# radios.net
KiCad netlist of a schematic drawn in Altium Designer
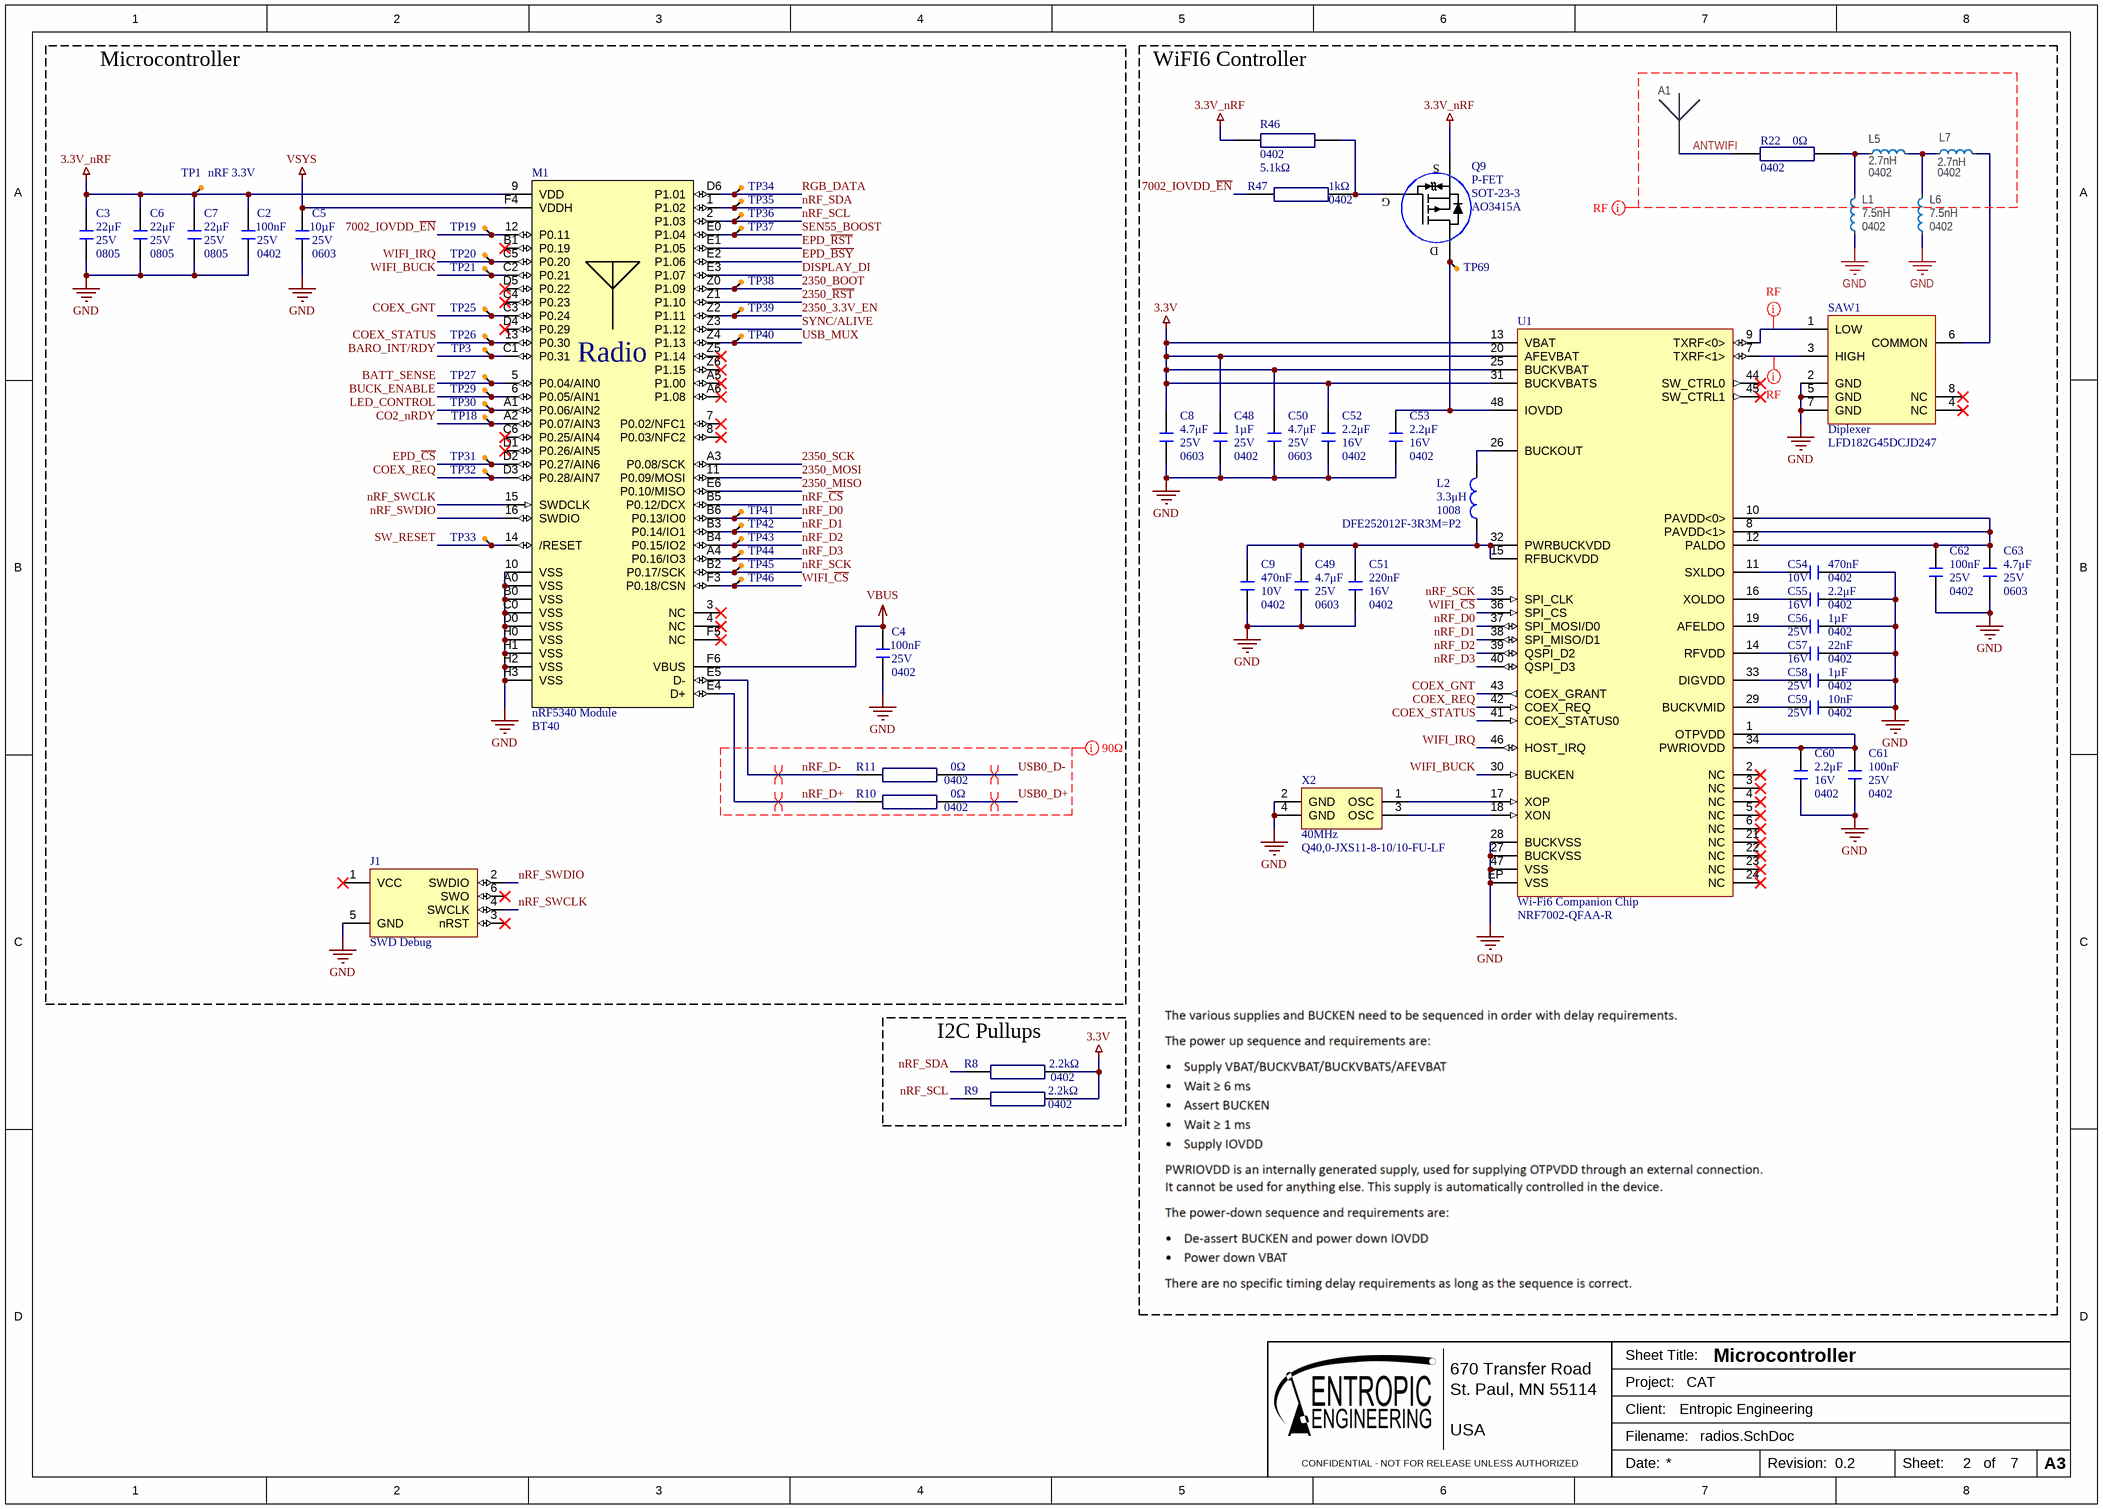
[diagram p0: radios.SchDoc]

(export (version "E")
  (design (tool "Eeschema 10.0.6"))
  (components
    (comp (ref "A1")
      (value "~")
      (footprint "NN03-320")
      (description "Dual-Band GNSS and Wi-Fi/BluetoothAntenna")
      (fields
        (field (name "PART NUMBER") "NN03-320")
        (field (name "MANUFACTURER") "Ignion")
        (field (name "AUTHOR") "rubr")
      )
      (libsource (lib "cat") (part "Antenna_NN03-320"))
    )
    (comp (ref "C2")
      (value "GRM155R71E104KE14D")
      (footprint "0402_capacitor")
      (description "100 nF, 25 V, X7R, 0402 Chip capacitor")
      (fields
        (field (name "MANUFACTURER") "Murata")
        (field (name "TOLERANCE") "10%")
        (field (name "VOLTAGE RATING") "25V")
        (field (name "CASE CODE (IMPERIAL)") "0402")
        (field (name "CAPACITANCE") "100nF")
      )
      (libsource (lib "cat") (part "GRM155R71E104KE14D"))
    )
    (comp (ref "C3")
      (value "22μF")
      (footprint "0805_capacitor")
      (description "22 μF, 25 V, X5R, 0805 Chip capacitor")
      (fields
        (field (name "MANUFACTURER") "Murata")
        (field (name "MANUFACTURER PART NUMBER") "GRT21BR61E226ME13L")
        (field (name "RATED DC VOLTAGE (URDC)") "25V")
        (field (name "CASE/PACKAGE") "0805")
      )
      (libsource (lib "cat") (part "GRT21BR61E226ME13L"))
    )
    (comp (ref "C4")
      (value "GRM155R71E104KE14D")
      (footprint "0402_capacitor")
      (description "100 nF, 25 V, X7R, 0402 Chip capacitor")
      (fields
        (field (name "MANUFACTURER") "Murata")
        (field (name "TOLERANCE") "10%")
        (field (name "VOLTAGE RATING") "25V")
        (field (name "CASE CODE (IMPERIAL)") "0402")
        (field (name "CAPACITANCE") "100nF")
      )
      (libsource (lib "cat") (part "GRM155R71E104KE14D"))
    )
    (comp (ref "C5")
      (value "10µF")
      (footprint "0603_capacitor")
      (description "10 µF, 25 V, X5R, 0603 Chip capacitor")
      (fields
        (field (name "MANUFACTURER") "Samsung")
        (field (name "TOLERANCE") "20%")
        (field (name "VOLTAGE RATING") "25V")
        (field (name "CASE CODE (IMPERIAL)") "0603")
      )
      (libsource (lib "cat") (part "CL10A106MA8NRNC"))
    )
    (comp (ref "C6")
      (value "22μF")
      (footprint "0805_capacitor")
      (description "22 μF, 25 V, X5R, 0805 Chip capacitor")
      (fields
        (field (name "MANUFACTURER") "Murata")
        (field (name "MANUFACTURER PART NUMBER") "GRT21BR61E226ME13L")
        (field (name "RATED DC VOLTAGE (URDC)") "25V")
        (field (name "CASE/PACKAGE") "0805")
      )
      (libsource (lib "cat") (part "GRT21BR61E226ME13L"))
    )
    (comp (ref "C7")
      (value "22μF")
      (footprint "0805_capacitor")
      (description "22 μF, 25 V, X5R, 0805 Chip capacitor")
      (fields
        (field (name "MANUFACTURER") "Murata")
        (field (name "MANUFACTURER PART NUMBER") "GRT21BR61E226ME13L")
        (field (name "RATED DC VOLTAGE (URDC)") "25V")
        (field (name "CASE/PACKAGE") "0805")
      )
      (libsource (lib "cat") (part "GRT21BR61E226ME13L"))
    )
    (comp (ref "C8")
      (value "4.7μF")
      (footprint "0603_capacitor")
      (description "4.7 μF, 25 V, X7R, 0603 Chip capacitor")
      (fields
        (field (name "MANUFACTURER") "TDK")
        (field (name "MANUFACTURER PART NUMBER") "C1608X5R1E475K080AC")
        (field (name "VOLTAGE RATING") "25V")
        (field (name "CASE/PACKAGE") "0603")
      )
      (libsource (lib "cat") (part "C1608X5R1E475K080AC"))
    )
    (comp (ref "C9")
      (value "CL05Y474KP5VPJC")
      (footprint "0402_capacitor")
      (description "470 nF, 10 V, X7S, 0402 Chip capacitor")
      (fields
        (field (name "MANUFACTURER") "Samsung")
        (field (name "CAPACITANCE") "470nF")
        (field (name "VOLTAGE RATING") "10V")
        (field (name "CASE/PACKAGE") "0402")
      )
      (libsource (lib "cat") (part "CL05Y474KP5VPJC"))
    )
    (comp (ref "C48")
      (value "GRM155R61E105KA12D")
      (footprint "0402_capacitor")
      (description "1 µF, 25 V, X5R, 0402 Chip capacitor")
      (fields
        (field (name "MANUFACTURER") "Murata")
        (field (name "HOUSE_PART_NUMBER") "C-1uF-0402-002")
        (field (name "SIZE CODE") "0402")
        (field (name "CAPACITANCE") "1µF")
        (field (name "VOLTAGE") "25V")
      )
      (libsource (lib "cat") (part "GRM155R61E105KA12D"))
    )
    (comp (ref "C49")
      (value "4.7μF")
      (footprint "0603_capacitor")
      (description "4.7 μF, 25 V, X7R, 0603 Chip capacitor")
      (fields
        (field (name "MANUFACTURER") "TDK")
        (field (name "MANUFACTURER PART NUMBER") "C1608X5R1E475K080AC")
        (field (name "VOLTAGE RATING") "25V")
        (field (name "CASE/PACKAGE") "0603")
      )
      (libsource (lib "cat") (part "C1608X5R1E475K080AC"))
    )
    (comp (ref "C50")
      (value "4.7μF")
      (footprint "0603_capacitor")
      (description "4.7 μF, 25 V, X7R, 0603 Chip capacitor")
      (fields
        (field (name "MANUFACTURER") "TDK")
        (field (name "MANUFACTURER PART NUMBER") "C1608X5R1E475K080AC")
        (field (name "VOLTAGE RATING") "25V")
        (field (name "CASE/PACKAGE") "0603")
      )
      (libsource (lib "cat") (part "C1608X5R1E475K080AC"))
    )
    (comp (ref "C51")
      (value "220nF")
      (footprint "0402_capacitor")
      (description "220 nF, 16 V, X7R, 0402 Chip capacitor")
      (fields
        (field (name "MANUFACTURER") "Murata")
        (field (name "MANUFACTURER PART NUMBER") "GCM155R71C224KE02D")
        (field (name "VOLTAGE RATING") "16V")
        (field (name "CASE/PACKAGE") "0402")
      )
      (libsource (lib "cat") (part "GCM155R71C224KE02D"))
    )
    (comp (ref "C52")
      (value "2.2μF")
      (footprint "0402_capacitor")
      (description "2.2 µF, 16 V, X7T, 0402 Chip capacitor")
      (fields
        (field (name "MANUFACTURER") "Murata")
        (field (name "MANUFACTURER PART NUMBER") "GRM155D71C225ME11D")
        (field (name "VOLTAGE RATING") "16V")
        (field (name "CASE/PACKAGE") "0402")
      )
      (libsource (lib "cat") (part "GRM155D71C225ME11D"))
    )
    (comp (ref "C53")
      (value "2.2μF")
      (footprint "0402_capacitor")
      (description "2.2 µF, 16 V, X7T, 0402 Chip capacitor")
      (fields
        (field (name "MANUFACTURER") "Murata")
        (field (name "MANUFACTURER PART NUMBER") "GRM155D71C225ME11D")
        (field (name "VOLTAGE RATING") "16V")
        (field (name "CASE/PACKAGE") "0402")
      )
      (libsource (lib "cat") (part "GRM155D71C225ME11D"))
    )
    (comp (ref "C54")
      (value "CL05Y474KP5VPJC")
      (footprint "0402_capacitor")
      (description "470 nF, 10 V, X7S, 0402 Chip capacitor")
      (fields
        (field (name "MANUFACTURER") "Samsung")
        (field (name "CAPACITANCE") "470nF")
        (field (name "VOLTAGE RATING") "10V")
        (field (name "CASE/PACKAGE") "0402")
      )
      (libsource (lib "cat") (part "CL05Y474KP5VPJC"))
    )
    (comp (ref "C55")
      (value "2.2μF")
      (footprint "0402_capacitor")
      (description "2.2 µF, 16 V, X7T, 0402 Chip capacitor")
      (fields
        (field (name "MANUFACTURER") "Murata")
        (field (name "MANUFACTURER PART NUMBER") "GRM155D71C225ME11D")
        (field (name "VOLTAGE RATING") "16V")
        (field (name "CASE/PACKAGE") "0402")
      )
      (libsource (lib "cat") (part "GRM155D71C225ME11D"))
    )
    (comp (ref "C56")
      (value "GRM155R61E105KA12D")
      (footprint "0402_capacitor")
      (description "1 µF, 25 V, X5R, 0402 Chip capacitor")
      (fields
        (field (name "MANUFACTURER") "Murata")
        (field (name "HOUSE_PART_NUMBER") "C-1uF-0402-002")
        (field (name "SIZE CODE") "0402")
        (field (name "CAPACITANCE") "1µF")
        (field (name "VOLTAGE") "25V")
      )
      (libsource (lib "cat") (part "GRM155R61E105KA12D"))
    )
    (comp (ref "C57")
      (value "22nF")
      (footprint "0402_capacitor")
      (description "22 nF, 16 V, X7R, 0402 Chip capacitor")
      (fields
        (field (name "MANUFACTURER") "KEMET")
        (field (name "MANUFACTURER PART NUMBER") "C0402C223K4RECAUTO")
        (field (name "VOLTAGE RATING") "16V")
        (field (name "CASE/PACKAGE") "0402")
      )
      (libsource (lib "cat") (part "C0402C223K4RECAUTO"))
    )
    (comp (ref "C58")
      (value "GRM155R61E105KA12D")
      (footprint "0402_capacitor")
      (description "1 µF, 25 V, X5R, 0402 Chip capacitor")
      (fields
        (field (name "MANUFACTURER") "Murata")
        (field (name "HOUSE_PART_NUMBER") "C-1uF-0402-002")
        (field (name "SIZE CODE") "0402")
        (field (name "CAPACITANCE") "1µF")
        (field (name "VOLTAGE") "25V")
      )
      (libsource (lib "cat") (part "GRM155R61E105KA12D"))
    )
    (comp (ref "C59")
      (value "CL05B103KA5NNNC")
      (footprint "0402_capacitor")
      (description "10 nF, 25 V, X7R, 0402 Chip capacitor")
      (fields
        (field (name "MANUFACTURER") "Samsung")
        (field (name "TOLERANCE") "10%")
        (field (name "CAPACITANCE") "10nF")
        (field (name "VOLTAGE RATING") "25V")
        (field (name "CASE CODE (IMPERIAL)") "0402")
      )
      (libsource (lib "cat") (part "CL05B103KA5NNNC"))
    )
    (comp (ref "C60")
      (value "2.2μF")
      (footprint "0402_capacitor")
      (description "2.2 µF, 16 V, X7T, 0402 Chip capacitor")
      (fields
        (field (name "MANUFACTURER") "Murata")
        (field (name "MANUFACTURER PART NUMBER") "GRM155D71C225ME11D")
        (field (name "VOLTAGE RATING") "16V")
        (field (name "CASE/PACKAGE") "0402")
      )
      (libsource (lib "cat") (part "GRM155D71C225ME11D"))
    )
    (comp (ref "C61")
      (value "GRM155R71E104KE14D")
      (footprint "0402_capacitor")
      (description "100 nF, 25 V, X7R, 0402 Chip capacitor")
      (fields
        (field (name "MANUFACTURER") "Murata")
        (field (name "TOLERANCE") "10%")
        (field (name "CASE CODE (IMPERIAL)") "0402")
        (field (name "VOLTAGE") "25V")
        (field (name "CAPACITANCE") "100nF")
      )
      (libsource (lib "cat") (part "GRM155R71E104KE14D"))
    )
    (comp (ref "C62")
      (value "GRM155R71E104KE14D")
      (footprint "0402_capacitor")
      (description "100 nF, 25 V, X7R, 0402 Chip capacitor")
      (fields
        (field (name "MANUFACTURER") "Murata")
        (field (name "TOLERANCE") "10%")
        (field (name "CASE CODE (IMPERIAL)") "0402")
        (field (name "VOLTAGE") "25V")
        (field (name "CAPACITANCE") "100nF")
      )
      (libsource (lib "cat") (part "GRM155R71E104KE14D"))
    )
    (comp (ref "C63")
      (value "4.7μF")
      (footprint "0603_capacitor")
      (description "4.7 μF, 25 V, X7R, 0603 Chip capacitor")
      (fields
        (field (name "MANUFACTURER") "TDK")
        (field (name "MANUFACTURER PART NUMBER") "C1608X5R1E475K080AC")
        (field (name "VOLTAGE RATING") "25V")
        (field (name "CASE/PACKAGE") "0603")
      )
      (libsource (lib "cat") (part "C1608X5R1E475K080AC"))
    )
    (comp (ref "J1")
      (value "SWD Debug")
      (footprint "debug_header_dual")
      (description "Mates with TC-2030-CTX-NL")
      (fields (field (name "HOUSE_PART_NUMBER") "type-value-case-grade"))
      (libsource (lib "cat") (part "TAG_CONN_CTX"))
    )
    (comp (ref "L1")
      (value "7.5nH")
      (footprint "INDC1005X04L")
      (description "Inductor, 550mA, ±2%, 240mΩ")
      (fields
        (field (name "PART NUMBER") "L0402-7n5-Multilayer_Murata")
        (field (name "MANUFACTURER") "Murata")
        (field (name "FOOTPRINT DOC") "0402")
        (field (name "AUTHOR") "hany")
      )
      (libsource (lib "cat") (part "IND"))
    )
    (comp (ref "L2")
      (value "3.3μH")
      (footprint "INDC2520X12N")
      (description "3.3 μH, 1.8 A, 1008 Inductor")
      (fields
        (field (name "MANUFACTURER") "Murata")
        (field (name "TOLERANCE") "20%")
        (field (name "CASE CODE (IMPERIAL)") "1008")
        (field (name "MANUFACTURER PART NUMBER") "DFE252012F-3R3M=P2")
      )
      (libsource (lib "cat") (part "DFE252012F-3R3M=P2"))
    )
    (comp (ref "L5")
      (value "2.7nH")
      (footprint "INDC1005X04L")
      (description "Inductor, 800mA, ±2%, 120mΩ")
      (fields
        (field (name "PART NUMBER") "L0402-2n7-Multilayer_Murata")
        (field (name "MANUFACTURER") "Murata")
        (field (name "FOOTPRINT DOC") "0402")
        (field (name "AUTHOR") "hany")
      )
      (libsource (lib "cat") (part "IND"))
    )
    (comp (ref "L6")
      (value "7.5nH")
      (footprint "INDC1005X04L")
      (description "Inductor, 550mA, ±2%, 240mΩ")
      (fields
        (field (name "PART NUMBER") "L0402-7n5-Multilayer_Murata")
        (field (name "MANUFACTURER") "Murata")
        (field (name "FOOTPRINT DOC") "0402")
        (field (name "AUTHOR") "hany")
      )
      (libsource (lib "cat") (part "IND"))
    )
    (comp (ref "L7")
      (value "2.7nH")
      (footprint "INDC1005X04L")
      (description "Inductor, 800mA, ±2%, 120mΩ")
      (fields
        (field (name "PART NUMBER") "L0402-2n7-Multilayer_Murata")
        (field (name "MANUFACTURER") "Murata")
        (field (name "FOOTPRINT DOC") "0402")
        (field (name "AUTHOR") "hany")
      )
      (libsource (lib "cat") (part "IND"))
    )
    (comp (ref "M1")
      (value "nRF5340 Module")
      (footprint "BT40")
      (description "Bluetooth Module: 802.15.1 BLE 5.1, 802.15.4, nRF5340, PCB trace antenna")
      (fields (field (name "MANUFACTURER") "Fanstel") (field (name "MANUFACTURER PART NUMBER") "BT40"))
      (libsource (lib "cat") (part "BT40"))
    )
    (comp (ref "Q9")
      (value "P-FET")
      (footprint "SOT95P280X115-3N")
      (description "P-FET, 30V, 6A, SOT-23-3")
      (fields
        (field (name "MANUFACTURER") "Alpha & Omega Semiconductor")
        (field (name "CASE/PACKAGE") "SOT-23-3")
        (field (name "MANUFACTURER PART NUMBER") "AO3415A")
        (field (name "HOUSE_PART_NUMBER") "AO3415A")
      )
      (libsource (lib "cat") (part "AO3415A"))
    )
    (comp (ref "R8")
      (value "2.2kΩ")
      (footprint "0402_resistor")
      (description "2.2 kΩ, 0402 Chip resistor")
      (fields
        (field (name "MANUFACTURER") "Yageo")
        (field (name "MANUFACTURER PART NUMBER") "RC0402FR-072K2L")
        (field (name "CASE/PACKAGE") "0402")
      )
      (libsource (lib "cat") (part "RC0402FR-072K2L"))
    )
    (comp (ref "R9")
      (value "2.2kΩ")
      (footprint "0402_resistor")
      (description "2.2 kΩ, 0402 Chip resistor")
      (fields
        (field (name "MANUFACTURER") "Yageo")
        (field (name "MANUFACTURER PART NUMBER") "RC0402FR-072K2L")
        (field (name "CASE/PACKAGE") "0402")
      )
      (libsource (lib "cat") (part "RC0402FR-072K2L"))
    )
    (comp (ref "R10")
      (value "0Ω")
      (footprint "0402_resistor")
      (description "0 Ω, 0402 Chip resistor (jumper)")
      (fields
        (field (name "MANUFACTURER") "Yageo")
        (field (name "TOLERANCE") "1%")
        (field (name "CASE/PACKAGE") "0402")
      )
      (libsource (lib "cat") (part "RC0402FR-070RL"))
    )
    (comp (ref "R11")
      (value "0Ω")
      (footprint "0402_resistor")
      (description "0 Ω, 0402 Chip resistor (jumper)")
      (fields
        (field (name "MANUFACTURER") "Yageo")
        (field (name "TOLERANCE") "1%")
        (field (name "CASE/PACKAGE") "0402")
      )
      (libsource (lib "cat") (part "RC0402FR-070RL"))
    )
    (comp (ref "R22")
      (value "0Ω")
      (footprint "0402_resistor")
      (description "0 Ω, 0402 Chip resistor (jumper)")
      (fields
        (field (name "MANUFACTURER") "Yageo")
        (field (name "MANUFACTURER PART NUMBER") "RC0402FR-070RL")
        (field (name "CASE/PACKAGE") "0402")
      )
      (libsource (lib "cat") (part "RC0402FR-070RL"))
    )
    (comp (ref "R46")
      (value "5.1kΩ")
      (footprint "0402_resistor")
      (description "5.1 kΩ, 0402 Chip resistor")
      (fields
        (field (name "MANUFACTURER") "Yageo")
        (field (name "MANUFACTURER PART NUMBER") "RC0402FR-075K1L")
        (field (name "CASE/PACKAGE") "0402")
      )
      (libsource (lib "cat") (part "RC0402FR-075K1L"))
    )
    (comp (ref "R47")
      (value "1kΩ")
      (footprint "0402_resistor")
      (description "1 kΩ, 0402 Chip resistor")
      (fields
        (field (name "MANUFACTURER") "Yageo")
        (field (name "MANUFACTURER PART NUMBER") "RC0402JR-071KL")
        (field (name "CASE/PACKAGE") "0402")
      )
      (libsource (lib "cat") (part "RC0402JR-071KL"))
    )
    (comp (ref "SAW1")
      (value "Diplexer")
      (footprint "CAF-50P160X80-6N")
      (description "Murata Manufacturing Co., Ltd. SMD")
      (fields
        (field (name "MANUFACTURER") "Murata")
        (field (name "MANUFACTURER PART NUMBER") "LFD182G45DCJD247")
      )
      (libsource (lib "cat") (part "LFD182G45DCJD247"))
    )
    (comp (ref "TP1")
      (value "nRF 3.3V")
      (footprint "test_point-1")
      (description "Test point")
      (libsource (lib "cat") (part "test_point-1"))
    )
    (comp (ref "TP3")
      (value "test_point-1")
      (footprint "test_point-1")
      (description "Test point")
      (libsource (lib "cat") (part "test_point-1"))
    )
    (comp (ref "TP18")
      (value "test_point-1")
      (footprint "test_point-1")
      (description "Test point")
      (libsource (lib "cat") (part "test_point-1"))
    )
    (comp (ref "TP19")
      (value "test_point-1")
      (footprint "test_point-1")
      (description "Test point")
      (libsource (lib "cat") (part "test_point-1"))
    )
    (comp (ref "TP20")
      (value "test_point-1")
      (footprint "test_point-1")
      (description "Test point")
      (libsource (lib "cat") (part "test_point-1"))
    )
    (comp (ref "TP21")
      (value "test_point-1")
      (footprint "test_point-1")
      (description "Test point")
      (libsource (lib "cat") (part "test_point-1"))
    )
    (comp (ref "TP25")
      (value "test_point-1")
      (footprint "test_point-1")
      (description "Test point")
      (libsource (lib "cat") (part "test_point-1"))
    )
    (comp (ref "TP26")
      (value "test_point-1")
      (footprint "test_point-1")
      (description "Test point")
      (libsource (lib "cat") (part "test_point-1"))
    )
    (comp (ref "TP27")
      (value "test_point-1")
      (footprint "test_point-1")
      (description "Test point")
      (libsource (lib "cat") (part "test_point-1"))
    )
    (comp (ref "TP29")
      (value "test_point-1")
      (footprint "test_point-1")
      (description "Test point")
      (libsource (lib "cat") (part "test_point-1"))
    )
    (comp (ref "TP30")
      (value "test_point-1")
      (footprint "test_point-1")
      (description "Test point")
      (libsource (lib "cat") (part "test_point-1"))
    )
    (comp (ref "TP31")
      (value "~")
      (footprint "test_point-1")
      (description "Test point")
      (libsource (lib "cat") (part "test_point-1"))
    )
    (comp (ref "TP32")
      (value "test_point-1")
      (footprint "test_point-1")
      (description "Test point")
      (libsource (lib "cat") (part "test_point-1"))
    )
    (comp (ref "TP33")
      (value "test_point-1")
      (footprint "test_point-1")
      (description "Test point")
      (libsource (lib "cat") (part "test_point-1"))
    )
    (comp (ref "TP34")
      (value "test_point-1")
      (footprint "test_point-1")
      (description "Test point")
      (libsource (lib "cat") (part "test_point-1"))
    )
    (comp (ref "TP35")
      (value "test_point-1")
      (footprint "test_point-1")
      (description "Test point")
      (libsource (lib "cat") (part "test_point-1"))
    )
    (comp (ref "TP36")
      (value "test_point-1")
      (footprint "test_point-1")
      (description "Test point")
      (libsource (lib "cat") (part "test_point-1"))
    )
    (comp (ref "TP37")
      (value "test_point-1")
      (footprint "test_point-1")
      (description "Test point")
      (libsource (lib "cat") (part "test_point-1"))
    )
    (comp (ref "TP38")
      (value "test_point-1")
      (footprint "test_point-1")
      (description "Test point")
      (libsource (lib "cat") (part "test_point-1"))
    )
    (comp (ref "TP39")
      (value "test_point-1")
      (footprint "test_point-1")
      (description "Test point")
      (libsource (lib "cat") (part "test_point-1"))
    )
    (comp (ref "TP40")
      (value "test_point-1")
      (footprint "test_point-1")
      (description "Test point")
      (libsource (lib "cat") (part "test_point-1"))
    )
    (comp (ref "TP41")
      (value "test_point-1")
      (footprint "test_point-1")
      (description "Test point")
      (libsource (lib "cat") (part "test_point-1"))
    )
    (comp (ref "TP42")
      (value "test_point-1")
      (footprint "test_point-1")
      (description "Test point")
      (libsource (lib "cat") (part "test_point-1"))
    )
    (comp (ref "TP43")
      (value "test_point-1")
      (footprint "test_point-1")
      (description "Test point")
      (libsource (lib "cat") (part "test_point-1"))
    )
    (comp (ref "TP44")
      (value "test_point-1")
      (footprint "test_point-1")
      (description "Test point")
      (libsource (lib "cat") (part "test_point-1"))
    )
    (comp (ref "TP45")
      (value "test_point-1")
      (footprint "test_point-1")
      (description "Test point")
      (libsource (lib "cat") (part "test_point-1"))
    )
    (comp (ref "TP46")
      (value "test_point-1")
      (footprint "test_point-1")
      (description "Test point")
      (libsource (lib "cat") (part "test_point-1"))
    )
    (comp (ref "TP69")
      (value "nRF IOVDD")
      (footprint "test_point-1")
      (description "Test point")
      (libsource (lib "cat") (part "test_point-1"))
    )
    (comp (ref "U1")
      (value "Wi-Fi6 Companion Chip")
      (footprint "QFN40P600X600X60-48N")
      (description "Wi-Fi 6 Module IEEE 802.11a/b/g/n/ac/ax DSSS/CCK/HT 2.4GHz/5GHz 86Mbps 48-Pin QFN EP T/R")
      (fields
        (field (name "MANUFACTURER") "Nordic Semiconductor")
        (field (name "MANUFACTURER PART NUMBER") "NRF7002-QFAA-R")
      )
      (libsource (lib "cat") (part "NRF7002-QFAA-R"))
    )
    (comp (ref "X2")
      (value "40MHz")
      (footprint "1612_CRYSTAL")
      (description "Crystal 40.0000MHZ 8PF SMD")
      (fields
        (field (name "MANUFACTURER") "Jauch")
        (field (name "MANUFACTURER PART NUMBER") "Q40,0-JXS11-8-10/10-FU-LF")
      )
      (libsource (lib "cat") (part "Q40,0-JXS11-8-10/10-FU-LF"))
    )
  )
  (nets
    (net (code "1") (name "/2350_3.3V_EN") (class "Default")
      (node (ref "M1") (pin "Z2") (pinfunction "P1.11_Z2") (pintype "bidirectional"))
      (node (ref "TP39") (pin "1") (pinfunction "1_1") (pintype "passive"))
    )
    (net (code "2") (name "/2350_BOOT") (class "Default")
      (node (ref "M1") (pin "Z0") (pinfunction "P1.09_Z0") (pintype "bidirectional"))
      (node (ref "TP38") (pin "1") (pinfunction "1_1") (pintype "passive"))
    )
    (net (code "3") (name "/2350_MISO") (class "Default")
      (node (ref "M1") (pin "E6") (pinfunction "P0.10/MISO_E6") (pintype "bidirectional"))
    )
    (net (code "4") (name "/2350_MOSI") (class "Default")
      (node (ref "M1") (pin "11") (pinfunction "P0.09/MOSI_11") (pintype "bidirectional"))
    )
    (net (code "5") (name "/2350_SCK") (class "Default")
      (node (ref "M1") (pin "A3") (pinfunction "P0.08/SCK_A3") (pintype "bidirectional"))
    )
    (net (code "6") (name "/2350_~{RST}") (class "Default")
      (node (ref "M1") (pin "Z1") (pinfunction "P1.10_Z1") (pintype "bidirectional"))
    )
    (net (code "7") (name "/7002_IOVDD_~{EN}") (class "Default")
      (node (ref "M1") (pin "12") (pinfunction "P0.11_12") (pintype "bidirectional"))
      (node (ref "R47") (pin "1") (pinfunction "1_1") (pintype "passive"))
      (node (ref "TP19") (pin "1") (pinfunction "1_1") (pintype "passive"))
    )
    (net (code "8") (name "/ANTWIFI") (class "Default")
      (node (ref "A1") (pin "4") (pinfunction "Feed1_4") (pintype "passive"))
      (node (ref "R22") (pin "2") (pinfunction "2_2") (pintype "passive"))
    )
    (net (code "9") (name "/BARO_INT{slash}RDY") (class "Default")
      (node (ref "M1") (pin "C1") (pinfunction "P0.31_C1") (pintype "bidirectional"))
      (node (ref "TP3") (pin "1") (pinfunction "1_1") (pintype "passive"))
    )
    (net (code "10") (name "/BATT_SENSE") (class "Default")
      (node (ref "M1") (pin "5") (pinfunction "P0.04/AIN0_5") (pintype "bidirectional"))
      (node (ref "TP27") (pin "1") (pinfunction "1_1") (pintype "passive"))
    )
    (net (code "11") (name "/BUCK_ENABLE") (class "Default")
      (node (ref "M1") (pin "6") (pinfunction "P0.05/AIN1_6") (pintype "bidirectional"))
      (node (ref "TP29") (pin "1") (pinfunction "1_1") (pintype "passive"))
    )
    (net (code "12") (name "/CO2_nRDY") (class "Default")
      (node (ref "M1") (pin "A2") (pinfunction "P0.07/AIN3_A2") (pintype "bidirectional"))
      (node (ref "TP18") (pin "1") (pinfunction "1_1") (pintype "passive"))
    )
    (net (code "13") (name "/COEX_GNT") (class "Default")
      (node (ref "M1") (pin "C3") (pinfunction "P0.24_C3") (pintype "bidirectional"))
      (node (ref "TP25") (pin "1") (pinfunction "1_1") (pintype "passive"))
      (node (ref "U1") (pin "43") (pinfunction "COEX_GRANT_43") (pintype "output"))
    )
    (net (code "14") (name "/COEX_REQ") (class "Default")
      (node (ref "M1") (pin "D3") (pinfunction "P0.28/AIN7_D3") (pintype "bidirectional"))
      (node (ref "TP32") (pin "1") (pinfunction "1_1") (pintype "passive"))
      (node (ref "U1") (pin "42") (pinfunction "COEX_REQ_42") (pintype "input"))
    )
    (net (code "15") (name "/COEX_STATUS") (class "Default")
      (node (ref "M1") (pin "13") (pinfunction "P0.30_13") (pintype "bidirectional"))
      (node (ref "TP26") (pin "1") (pinfunction "1_1") (pintype "passive"))
      (node (ref "U1") (pin "41") (pinfunction "COEX_STATUS0_41") (pintype "input"))
    )
    (net (code "16") (name "/DISPLAY_DI") (class "Default")
      (node (ref "M1") (pin "E3") (pinfunction "P1.07_E3") (pintype "bidirectional"))
    )
    (net (code "17") (name "/EPD_~{BSY}") (class "Default")
      (node (ref "M1") (pin "E2") (pinfunction "P1.06_E2") (pintype "bidirectional"))
    )
    (net (code "18") (name "/EPD_~{CS}") (class "Default")
      (node (ref "M1") (pin "D2") (pinfunction "P0.27/AIN6_D2") (pintype "bidirectional"))
      (node (ref "TP31") (pin "1") (pinfunction "1_1") (pintype "passive"))
    )
    (net (code "19") (name "/EPD_~{RST}") (class "Default")
      (node (ref "M1") (pin "E1") (pinfunction "P1.05_E1") (pintype "bidirectional"))
    )
    (net (code "20") (name "/LED_CONTROL") (class "Default")
      (node (ref "M1") (pin "A1") (pinfunction "P0.06/AIN2_A1") (pintype "bidirectional"))
      (node (ref "TP30") (pin "1") (pinfunction "1_1") (pintype "passive"))
    )
    (net (code "21") (name "/RGB_DATA") (class "Default")
      (node (ref "M1") (pin "D6") (pinfunction "P1.01_D6") (pintype "bidirectional"))
      (node (ref "TP34") (pin "1") (pinfunction "1_1") (pintype "passive"))
    )
    (net (code "22") (name "/SEN55_BOOST") (class "Default")
      (node (ref "M1") (pin "E0") (pinfunction "P1.04_E0") (pintype "bidirectional"))
      (node (ref "TP37") (pin "1") (pinfunction "1_1") (pintype "passive"))
    )
    (net (code "23") (name "/SW_RESET") (class "Default")
      (node (ref "M1") (pin "14") (pinfunction "/RESET_14") (pintype "bidirectional"))
      (node (ref "TP33") (pin "1") (pinfunction "1_1") (pintype "passive"))
    )
    (net (code "24") (name "/SYNC{slash}ALIVE") (class "Default")
      (node (ref "M1") (pin "Z3") (pinfunction "P1.12_Z3") (pintype "bidirectional"))
    )
    (net (code "25") (name "/USB0_D+") (class "Default")
      (node (ref "R10") (pin "1") (pinfunction "1_1") (pintype "passive"))
    )
    (net (code "26") (name "/USB0_D-") (class "Default")
      (node (ref "R11") (pin "1") (pinfunction "1_1") (pintype "passive"))
    )
    (net (code "27") (name "/USB_MUX") (class "Default")
      (node (ref "M1") (pin "Z4") (pinfunction "P1.13_Z4") (pintype "bidirectional"))
      (node (ref "TP40") (pin "1") (pinfunction "1_1") (pintype "passive"))
    )
    (net (code "28") (name "/WIFI_BUCK") (class "Default")
      (node (ref "M1") (pin "C2") (pinfunction "P0.21_C2") (pintype "bidirectional"))
      (node (ref "TP21") (pin "1") (pinfunction "1_1") (pintype "passive"))
      (node (ref "U1") (pin "30") (pinfunction "BUCKEN_30") (pintype "input"))
    )
    (net (code "29") (name "/WIFI_IRQ") (class "Default")
      (node (ref "M1") (pin "C5") (pinfunction "P0.20_C5") (pintype "bidirectional"))
      (node (ref "TP20") (pin "1") (pinfunction "1_1") (pintype "passive"))
      (node (ref "U1") (pin "46") (pinfunction "HOST_IRQ_46") (pintype "bidirectional"))
    )
    (net (code "30") (name "/WIFI_~{CS}") (class "Default")
      (node (ref "M1") (pin "F3") (pinfunction "P0.18/CSN_F3") (pintype "bidirectional"))
      (node (ref "TP46") (pin "1") (pinfunction "1_1") (pintype "passive"))
      (node (ref "U1") (pin "36") (pinfunction "SPI_CS_36") (pintype "input"))
    )
    (net (code "31") (name "/nRF_D+") (class "Default")
      (node (ref "M1") (pin "E4") (pinfunction "D+_E4") (pintype "bidirectional"))
      (node (ref "R10") (pin "2") (pinfunction "2_2") (pintype "passive"))
    )
    (net (code "32") (name "/nRF_D-") (class "Default")
      (node (ref "M1") (pin "E5") (pinfunction "D-_E5") (pintype "bidirectional"))
      (node (ref "R11") (pin "2") (pinfunction "2_2") (pintype "passive"))
    )
    (net (code "33") (name "/nRF_D0") (class "Default")
      (node (ref "M1") (pin "B6") (pinfunction "P0.13/IO0_B6") (pintype "bidirectional"))
      (node (ref "TP41") (pin "1") (pinfunction "1_1") (pintype "passive"))
      (node (ref "U1") (pin "37") (pinfunction "SPI_MOSI/D0_37") (pintype "bidirectional"))
    )
    (net (code "34") (name "/nRF_D1") (class "Default")
      (node (ref "M1") (pin "B3") (pinfunction "P0.14/IO1_B3") (pintype "bidirectional"))
      (node (ref "TP42") (pin "1") (pinfunction "1_1") (pintype "passive"))
      (node (ref "U1") (pin "38") (pinfunction "SPI_MISO/D1_38") (pintype "bidirectional"))
    )
    (net (code "35") (name "/nRF_D2") (class "Default")
      (node (ref "M1") (pin "B4") (pinfunction "P0.15/IO2_B4") (pintype "bidirectional"))
      (node (ref "TP43") (pin "1") (pinfunction "1_1") (pintype "passive"))
      (node (ref "U1") (pin "39") (pinfunction "QSPI_D2_39") (pintype "bidirectional"))
    )
    (net (code "36") (name "/nRF_D3") (class "Default")
      (node (ref "M1") (pin "A4") (pinfunction "P0.16/IO3_A4") (pintype "bidirectional"))
      (node (ref "TP44") (pin "1") (pinfunction "1_1") (pintype "passive"))
      (node (ref "U1") (pin "40") (pinfunction "QSPI_D3_40") (pintype "bidirectional"))
    )
    (net (code "37") (name "/nRF_SCK") (class "Default")
      (node (ref "M1") (pin "B2") (pinfunction "P0.17/SCK_B2") (pintype "bidirectional"))
      (node (ref "TP45") (pin "1") (pinfunction "1_1") (pintype "passive"))
      (node (ref "U1") (pin "35") (pinfunction "SPI_CLK_35") (pintype "input"))
    )
    (net (code "38") (name "/nRF_SCL") (class "Default")
      (node (ref "M1") (pin "2") (pinfunction "P1.03_2") (pintype "bidirectional"))
      (node (ref "R9") (pin "2") (pinfunction "2_2") (pintype "passive"))
      (node (ref "TP36") (pin "1") (pinfunction "1_1") (pintype "passive"))
    )
    (net (code "39") (name "/nRF_SDA") (class "Default")
      (node (ref "M1") (pin "1") (pinfunction "P1.02_1") (pintype "bidirectional"))
      (node (ref "R8") (pin "2") (pinfunction "2_2") (pintype "passive"))
      (node (ref "TP35") (pin "1") (pinfunction "1_1") (pintype "passive"))
    )
    (net (code "40") (name "/nRF_SWCLK") (class "Default")
      (node (ref "J1") (pin "4") (pinfunction "SWCLK_4") (pintype "bidirectional"))
      (node (ref "M1") (pin "15") (pinfunction "SWDCLK_15") (pintype "input"))
    )
    (net (code "41") (name "/nRF_SWDIO") (class "Default")
      (node (ref "J1") (pin "2") (pinfunction "SWDIO_2") (pintype "bidirectional"))
      (node (ref "M1") (pin "16") (pinfunction "SWDIO_16") (pintype "bidirectional"))
    )
    (net (code "42") (name "/nRF_~{CS}") (class "Default")
      (node (ref "M1") (pin "B5") (pinfunction "P0.12/DCX_B5") (pintype "bidirectional"))
    )
    (net (code "43") (name "3.3V") (class "Default")
      (node (ref "C48") (pin "2") (pinfunction "2_2") (pintype "passive"))
      (node (ref "C50") (pin "2") (pinfunction "2_2") (pintype "passive"))
      (node (ref "C52") (pin "2") (pinfunction "2_2") (pintype "passive"))
      (node (ref "C8") (pin "2") (pinfunction "2_2") (pintype "passive"))
      (node (ref "R8") (pin "1") (pinfunction "1_1") (pintype "passive"))
      (node (ref "R9") (pin "1") (pinfunction "1_1") (pintype "passive"))
      (node (ref "U1") (pin "13") (pinfunction "VBAT_13") (pintype "power_in"))
      (node (ref "U1") (pin "20") (pinfunction "AFEVBAT_20") (pintype "power_in"))
      (node (ref "U1") (pin "25") (pinfunction "BUCKVBAT_25") (pintype "power_in"))
      (node (ref "U1") (pin "31") (pinfunction "BUCKVBATS_31") (pintype "power_in"))
    )
    (net (code "44") (name "3.3V_nRF") (class "Default")
      (node (ref "C2") (pin "1") (pinfunction "1_1") (pintype "passive"))
      (node (ref "C3") (pin "2") (pinfunction "2_2") (pintype "passive"))
      (node (ref "C6") (pin "2") (pinfunction "2_2") (pintype "passive"))
      (node (ref "C7") (pin "2") (pinfunction "2_2") (pintype "passive"))
      (node (ref "M1") (pin "9") (pinfunction "VDD_9") (pintype "power_in"))
      (node (ref "Q9") (pin "2") (pinfunction "S_2") (pintype "power_in"))
      (node (ref "R46") (pin "2") (pinfunction "2_2") (pintype "passive"))
      (node (ref "TP1") (pin "1") (pinfunction "1_1") (pintype "passive"))
    )
    (net (code "45") (name "GND") (class "Default")
      (node (ref "C2") (pin "2") (pinfunction "2_2") (pintype "passive"))
      (node (ref "C3") (pin "1") (pinfunction "1_1") (pintype "passive"))
      (node (ref "C4") (pin "2") (pinfunction "2_2") (pintype "passive"))
      (node (ref "C48") (pin "1") (pinfunction "1_1") (pintype "passive"))
      (node (ref "C49") (pin "1") (pinfunction "1_1") (pintype "passive"))
      (node (ref "C5") (pin "1") (pinfunction "1_1") (pintype "passive"))
      (node (ref "C50") (pin "1") (pinfunction "1_1") (pintype "passive"))
      (node (ref "C51") (pin "1") (pinfunction "1_1") (pintype "passive"))
      (node (ref "C52") (pin "1") (pinfunction "1_1") (pintype "passive"))
      (node (ref "C53") (pin "1") (pinfunction "1_1") (pintype "passive"))
      (node (ref "C54") (pin "1") (pinfunction "1_1") (pintype "passive"))
      (node (ref "C55") (pin "1") (pinfunction "1_1") (pintype "passive"))
      (node (ref "C56") (pin "1") (pinfunction "1_1") (pintype "passive"))
      (node (ref "C57") (pin "2") (pinfunction "2_2") (pintype "passive"))
      (node (ref "C58") (pin "1") (pinfunction "1_1") (pintype "passive"))
      (node (ref "C59") (pin "1") (pinfunction "1_1") (pintype "passive"))
      (node (ref "C6") (pin "1") (pinfunction "1_1") (pintype "passive"))
      (node (ref "C60") (pin "1") (pinfunction "1_1") (pintype "passive"))
      (node (ref "C61") (pin "2") (pinfunction "2_2") (pintype "passive"))
      (node (ref "C62") (pin "2") (pinfunction "2_2") (pintype "passive"))
      (node (ref "C63") (pin "1") (pinfunction "1_1") (pintype "passive"))
      (node (ref "C7") (pin "1") (pinfunction "1_1") (pintype "passive"))
      (node (ref "C8") (pin "1") (pinfunction "1_1") (pintype "passive"))
      (node (ref "C9") (pin "2") (pinfunction "2_2") (pintype "passive"))
      (node (ref "J1") (pin "5") (pinfunction "GND_5") (pintype "power_in"))
      (node (ref "L1") (pin "1") (pinfunction "1_1") (pintype "passive"))
      (node (ref "L6") (pin "1") (pinfunction "1_1") (pintype "passive"))
      (node (ref "M1") (pin "10") (pinfunction "VSS_10") (pintype "power_in"))
      (node (ref "M1") (pin "A0") (pinfunction "VSS_A0") (pintype "power_in"))
      (node (ref "M1") (pin "B0") (pinfunction "VSS_B0") (pintype "power_in"))
      (node (ref "M1") (pin "C0") (pinfunction "VSS_C0") (pintype "power_in"))
      (node (ref "M1") (pin "D0") (pinfunction "VSS_D0") (pintype "power_in"))
      (node (ref "M1") (pin "H0") (pinfunction "VSS_H0") (pintype "power_in"))
      (node (ref "M1") (pin "H1") (pinfunction "VSS_H1") (pintype "power_in"))
      (node (ref "M1") (pin "H2") (pinfunction "VSS_H2") (pintype "power_in"))
      (node (ref "M1") (pin "H3") (pinfunction "VSS_H3") (pintype "power_in"))
      (node (ref "SAW1") (pin "2") (pinfunction "GND_2") (pintype "power_in"))
      (node (ref "SAW1") (pin "5") (pinfunction "GND_5") (pintype "power_in"))
      (node (ref "SAW1") (pin "7") (pinfunction "GND_7") (pintype "power_in"))
      (node (ref "U1") (pin "27") (pinfunction "BUCKVSS_27") (pintype "power_in"))
      (node (ref "U1") (pin "28") (pinfunction "BUCKVSS_28") (pintype "power_in"))
      (node (ref "U1") (pin "47") (pinfunction "VSS_47") (pintype "power_in"))
      (node (ref "U1") (pin "EP") (pinfunction "VSS_EP") (pintype "power_in"))
      (node (ref "X2") (pin "2") (pinfunction "GND_2") (pintype "power_in"))
      (node (ref "X2") (pin "4") (pinfunction "GND_4") (pintype "power_in"))
    )
    (net (code "46") (name "Net-(L1-Pad2)") (class "Default")
      (node (ref "L1") (pin "2") (pinfunction "2_2") (pintype "passive"))
      (node (ref "L5") (pin "1") (pinfunction "1_1") (pintype "passive"))
      (node (ref "R22") (pin "1") (pinfunction "1_1") (pintype "passive"))
    )
    (net (code "47") (name "Net-(L5-Pad2)") (class "Default")
      (node (ref "L5") (pin "2") (pinfunction "2_2") (pintype "passive"))
      (node (ref "L6") (pin "2") (pinfunction "2_2") (pintype "passive"))
      (node (ref "L7") (pin "1") (pinfunction "1_1") (pintype "passive"))
    )
    (net (code "48") (name "Net-(Q9-D)") (class "Default")
      (node (ref "C53") (pin "2") (pinfunction "2_2") (pintype "passive"))
      (node (ref "Q9") (pin "3") (pinfunction "D_3") (pintype "power_in"))
      (node (ref "TP69") (pin "1") (pinfunction "1_1") (pintype "passive"))
      (node (ref "U1") (pin "48") (pinfunction "IOVDD_48") (pintype "power_in"))
    )
    (net (code "49") (name "Net-(Q9-G)") (class "Default")
      (node (ref "Q9") (pin "1") (pinfunction "G_1") (pintype "power_in"))
      (node (ref "R46") (pin "1") (pinfunction "1_1") (pintype "passive"))
      (node (ref "R47") (pin "2") (pinfunction "2_2") (pintype "passive"))
    )
    (net (code "50") (name "Net-(SAW1-COMMON)") (class "Default")
      (node (ref "L7") (pin "2") (pinfunction "2_2") (pintype "passive"))
      (node (ref "SAW1") (pin "6") (pinfunction "COMMON_6") (pintype "passive"))
    )
    (net (code "51") (name "Net-(SAW1-HIGH)") (class "Default")
      (node (ref "SAW1") (pin "3") (pinfunction "HIGH_3") (pintype "passive"))
      (node (ref "U1") (pin "7") (pinfunction "TXRF<1>_7") (pintype "bidirectional"))
    )
    (net (code "52") (name "Net-(SAW1-LOW)") (class "Default")
      (node (ref "SAW1") (pin "1") (pinfunction "LOW_1") (pintype "passive"))
      (node (ref "U1") (pin "9") (pinfunction "TXRF<0>_9") (pintype "bidirectional"))
    )
    (net (code "53") (name "Net-(U1-AFELDO)") (class "Default")
      (node (ref "C56") (pin "2") (pinfunction "2_2") (pintype "passive"))
      (node (ref "U1") (pin "19") (pinfunction "AFELDO_19") (pintype "power_in"))
    )
    (net (code "54") (name "Net-(U1-BUCKOUT)") (class "Default")
      (node (ref "L2") (pin "2") (pinfunction "2_2") (pintype "passive"))
      (node (ref "U1") (pin "26") (pinfunction "BUCKOUT_26") (pintype "power_in"))
    )
    (net (code "55") (name "Net-(U1-BUCKVMID)") (class "Default")
      (node (ref "C59") (pin "2") (pinfunction "2_2") (pintype "passive"))
      (node (ref "U1") (pin "29") (pinfunction "BUCKVMID_29") (pintype "power_in"))
    )
    (net (code "56") (name "Net-(U1-DIGVDD)") (class "Default")
      (node (ref "C58") (pin "2") (pinfunction "2_2") (pintype "passive"))
      (node (ref "U1") (pin "33") (pinfunction "DIGVDD_33") (pintype "power_in"))
    )
    (net (code "57") (name "Net-(U1-OTPVDD)") (class "Default")
      (node (ref "C60") (pin "2") (pinfunction "2_2") (pintype "passive"))
      (node (ref "C61") (pin "1") (pinfunction "1_1") (pintype "passive"))
      (node (ref "U1") (pin "1") (pinfunction "OTPVDD_1") (pintype "power_in"))
      (node (ref "U1") (pin "34") (pinfunction "PWRIOVDD_34") (pintype "power_in"))
    )
    (net (code "58") (name "Net-(U1-PALDO)") (class "Default")
      (node (ref "C62") (pin "1") (pinfunction "1_1") (pintype "passive"))
      (node (ref "C63") (pin "2") (pinfunction "2_2") (pintype "passive"))
      (node (ref "U1") (pin "10") (pinfunction "PAVDD<0>_10") (pintype "power_in"))
      (node (ref "U1") (pin "12") (pinfunction "PALDO_12") (pintype "power_in"))
      (node (ref "U1") (pin "8") (pinfunction "PAVDD<1>_8") (pintype "power_in"))
    )
    (net (code "59") (name "Net-(U1-PWRBUCKVDD)") (class "Default")
      (node (ref "C49") (pin "2") (pinfunction "2_2") (pintype "passive"))
      (node (ref "C51") (pin "2") (pinfunction "2_2") (pintype "passive"))
      (node (ref "C9") (pin "1") (pinfunction "1_1") (pintype "passive"))
      (node (ref "L2") (pin "1") (pinfunction "1_1") (pintype "passive"))
      (node (ref "U1") (pin "15") (pinfunction "RFBUCKVDD_15") (pintype "power_in"))
      (node (ref "U1") (pin "32") (pinfunction "PWRBUCKVDD_32") (pintype "power_in"))
    )
    (net (code "60") (name "Net-(U1-RFVDD)") (class "Default")
      (node (ref "C57") (pin "1") (pinfunction "1_1") (pintype "passive"))
      (node (ref "U1") (pin "14") (pinfunction "RFVDD_14") (pintype "power_in"))
    )
    (net (code "61") (name "Net-(U1-SXLDO)") (class "Default")
      (node (ref "C54") (pin "2") (pinfunction "2_2") (pintype "passive"))
      (node (ref "U1") (pin "11") (pinfunction "SXLDO_11") (pintype "power_in"))
    )
    (net (code "62") (name "Net-(U1-XOLDO)") (class "Default")
      (node (ref "C55") (pin "2") (pinfunction "2_2") (pintype "passive"))
      (node (ref "U1") (pin "16") (pinfunction "XOLDO_16") (pintype "power_in"))
    )
    (net (code "63") (name "Net-(U1-XON)") (class "Default")
      (node (ref "U1") (pin "18") (pinfunction "XON_18") (pintype "input"))
      (node (ref "X2") (pin "3") (pinfunction "OSC_3") (pintype "passive"))
    )
    (net (code "64") (name "Net-(U1-XOP)") (class "Default")
      (node (ref "U1") (pin "17") (pinfunction "XOP_17") (pintype "input"))
      (node (ref "X2") (pin "1") (pinfunction "OSC_1") (pintype "passive"))
    )
    (net (code "65") (name "VBUS") (class "Default")
      (node (ref "C4") (pin "1") (pinfunction "1_1") (pintype "passive"))
      (node (ref "M1") (pin "F6") (pinfunction "VBUS_F6") (pintype "power_in"))
    )
    (net (code "66") (name "VSYS") (class "Default")
      (node (ref "C5") (pin "2") (pinfunction "2_2") (pintype "passive"))
      (node (ref "M1") (pin "F4") (pinfunction "VDDH_F4") (pintype "power_in"))
    )
    (net (code "67") (name "unconnected-(A1-Feed2-Pad3)") (class "Default")
      (node (ref "A1") (pin "3") (pinfunction "Feed2_3") (pintype "passive"))
    )
    (net (code "68") (name "unconnected-(A1-GND-Pad2)") (class "Default")
      (node (ref "A1") (pin "2") (pinfunction "GND_2") (pintype "passive"))
    )
    (net (code "69") (name "unconnected-(A1-NC-Pad1)") (class "Default")
      (node (ref "A1") (pin "1") (pinfunction "NC_1") (pintype "passive"))
    )
    (net (code "70") (name "unconnected-(J1-SWO-Pad6)") (class "Default")
      (node (ref "J1") (pin "6") (pinfunction "SWO_6") (pintype "bidirectional+no_connect"))
    )
    (net (code "71") (name "unconnected-(J1-VCC-Pad1)") (class "Default")
      (node (ref "J1") (pin "1") (pinfunction "VCC_1") (pintype "power_in+no_connect"))
    )
    (net (code "72") (name "unconnected-(J1-nRST-Pad3)") (class "Default")
      (node (ref "J1") (pin "3") (pinfunction "nRST_3") (pintype "bidirectional+no_connect"))
    )
    (net (code "73") (name "unconnected-(M1-NC-Pad3)") (class "Default")
      (node (ref "M1") (pin "3") (pinfunction "NC_3") (pintype "passive+no_connect"))
    )
    (net (code "74") (name "unconnected-(M1-NC-Pad4)") (class "Default")
      (node (ref "M1") (pin "4") (pinfunction "NC_4") (pintype "passive+no_connect"))
    )
    (net (code "75") (name "unconnected-(M1-NC-PadF5)") (class "Default")
      (node (ref "M1") (pin "F5") (pinfunction "NC_F5") (pintype "passive+no_connect"))
    )
    (net (code "76") (name "unconnected-(M1-P0.02{slash}NFC1-Pad7)") (class "Default")
      (node (ref "M1") (pin "7") (pinfunction "P0.02/NFC1_7") (pintype "bidirectional+no_connect"))
    )
    (net (code "77") (name "unconnected-(M1-P0.03{slash}NFC2-Pad8)") (class "Default")
      (node (ref "M1") (pin "8") (pinfunction "P0.03/NFC2_8") (pintype "bidirectional+no_connect"))
    )
    (net (code "78") (name "unconnected-(M1-P0.19-PadB1)") (class "Default")
      (node (ref "M1") (pin "B1") (pinfunction "P0.19_B1") (pintype "bidirectional+no_connect"))
    )
    (net (code "79") (name "unconnected-(M1-P0.22-PadD5)") (class "Default")
      (node (ref "M1") (pin "D5") (pinfunction "P0.22_D5") (pintype "bidirectional+no_connect"))
    )
    (net (code "80") (name "unconnected-(M1-P0.23-PadC4)") (class "Default")
      (node (ref "M1") (pin "C4") (pinfunction "P0.23_C4") (pintype "bidirectional+no_connect"))
    )
    (net (code "81") (name "unconnected-(M1-P0.25{slash}AIN4-PadC6)") (class "Default")
      (node (ref "M1") (pin "C6") (pinfunction "P0.25/AIN4_C6") (pintype "bidirectional+no_connect"))
    )
    (net (code "82") (name "unconnected-(M1-P0.26{slash}AIN5-PadD1)") (class "Default")
      (node (ref "M1") (pin "D1") (pinfunction "P0.26/AIN5_D1") (pintype "bidirectional+no_connect"))
    )
    (net (code "83") (name "unconnected-(M1-P0.29-PadD4)") (class "Default")
      (node (ref "M1") (pin "D4") (pinfunction "P0.29_D4") (pintype "bidirectional+no_connect"))
    )
    (net (code "84") (name "unconnected-(M1-P1.00-PadA5)") (class "Default")
      (node (ref "M1") (pin "A5") (pinfunction "P1.00_A5") (pintype "bidirectional+no_connect"))
    )
    (net (code "85") (name "unconnected-(M1-P1.08-PadA6)") (class "Default")
      (node (ref "M1") (pin "A6") (pinfunction "P1.08_A6") (pintype "bidirectional+no_connect"))
    )
    (net (code "86") (name "unconnected-(M1-P1.14-PadZ5)") (class "Default")
      (node (ref "M1") (pin "Z5") (pinfunction "P1.14_Z5") (pintype "bidirectional+no_connect"))
    )
    (net (code "87") (name "unconnected-(M1-P1.15-PadZ6)") (class "Default")
      (node (ref "M1") (pin "Z6") (pinfunction "P1.15_Z6") (pintype "bidirectional+no_connect"))
    )
    (net (code "88") (name "unconnected-(SAW1-NC-Pad4)") (class "Default")
      (node (ref "SAW1") (pin "4") (pinfunction "NC_4") (pintype "passive+no_connect"))
    )
    (net (code "89") (name "unconnected-(SAW1-NC-Pad8)") (class "Default")
      (node (ref "SAW1") (pin "8") (pinfunction "NC_8") (pintype "passive+no_connect"))
    )
    (net (code "90") (name "unconnected-(U1-NC-Pad2)") (class "Default")
      (node (ref "U1") (pin "2") (pinfunction "NC_2") (pintype "passive+no_connect"))
    )
    (net (code "91") (name "unconnected-(U1-NC-Pad3)") (class "Default")
      (node (ref "U1") (pin "3") (pinfunction "NC_3") (pintype "passive+no_connect"))
    )
    (net (code "92") (name "unconnected-(U1-NC-Pad4)") (class "Default")
      (node (ref "U1") (pin "4") (pinfunction "NC_4") (pintype "passive+no_connect"))
    )
    (net (code "93") (name "unconnected-(U1-NC-Pad5)") (class "Default")
      (node (ref "U1") (pin "5") (pinfunction "NC_5") (pintype "passive+no_connect"))
    )
    (net (code "94") (name "unconnected-(U1-NC-Pad6)") (class "Default")
      (node (ref "U1") (pin "6") (pinfunction "NC_6") (pintype "passive+no_connect"))
    )
    (net (code "95") (name "unconnected-(U1-NC-Pad21)") (class "Default")
      (node (ref "U1") (pin "21") (pinfunction "NC_21") (pintype "passive+no_connect"))
    )
    (net (code "96") (name "unconnected-(U1-NC-Pad22)") (class "Default")
      (node (ref "U1") (pin "22") (pinfunction "NC_22") (pintype "passive+no_connect"))
    )
    (net (code "97") (name "unconnected-(U1-NC-Pad23)") (class "Default")
      (node (ref "U1") (pin "23") (pinfunction "NC_23") (pintype "passive+no_connect"))
    )
    (net (code "98") (name "unconnected-(U1-NC-Pad24)") (class "Default")
      (node (ref "U1") (pin "24") (pinfunction "NC_24") (pintype "passive+no_connect"))
    )
    (net (code "99") (name "unconnected-(U1-SW_CTRL0-Pad44)") (class "Default")
      (node (ref "U1") (pin "44") (pinfunction "SW_CTRL0_44") (pintype "output+no_connect"))
    )
    (net (code "100") (name "unconnected-(U1-SW_CTRL1-Pad45)") (class "Default")
      (node (ref "U1") (pin "45") (pinfunction "SW_CTRL1_45") (pintype "output+no_connect"))
    )
  )
)
